# RP2350_CWHusky.net
KiCad netlist of a schematic drawn in Altium Designer
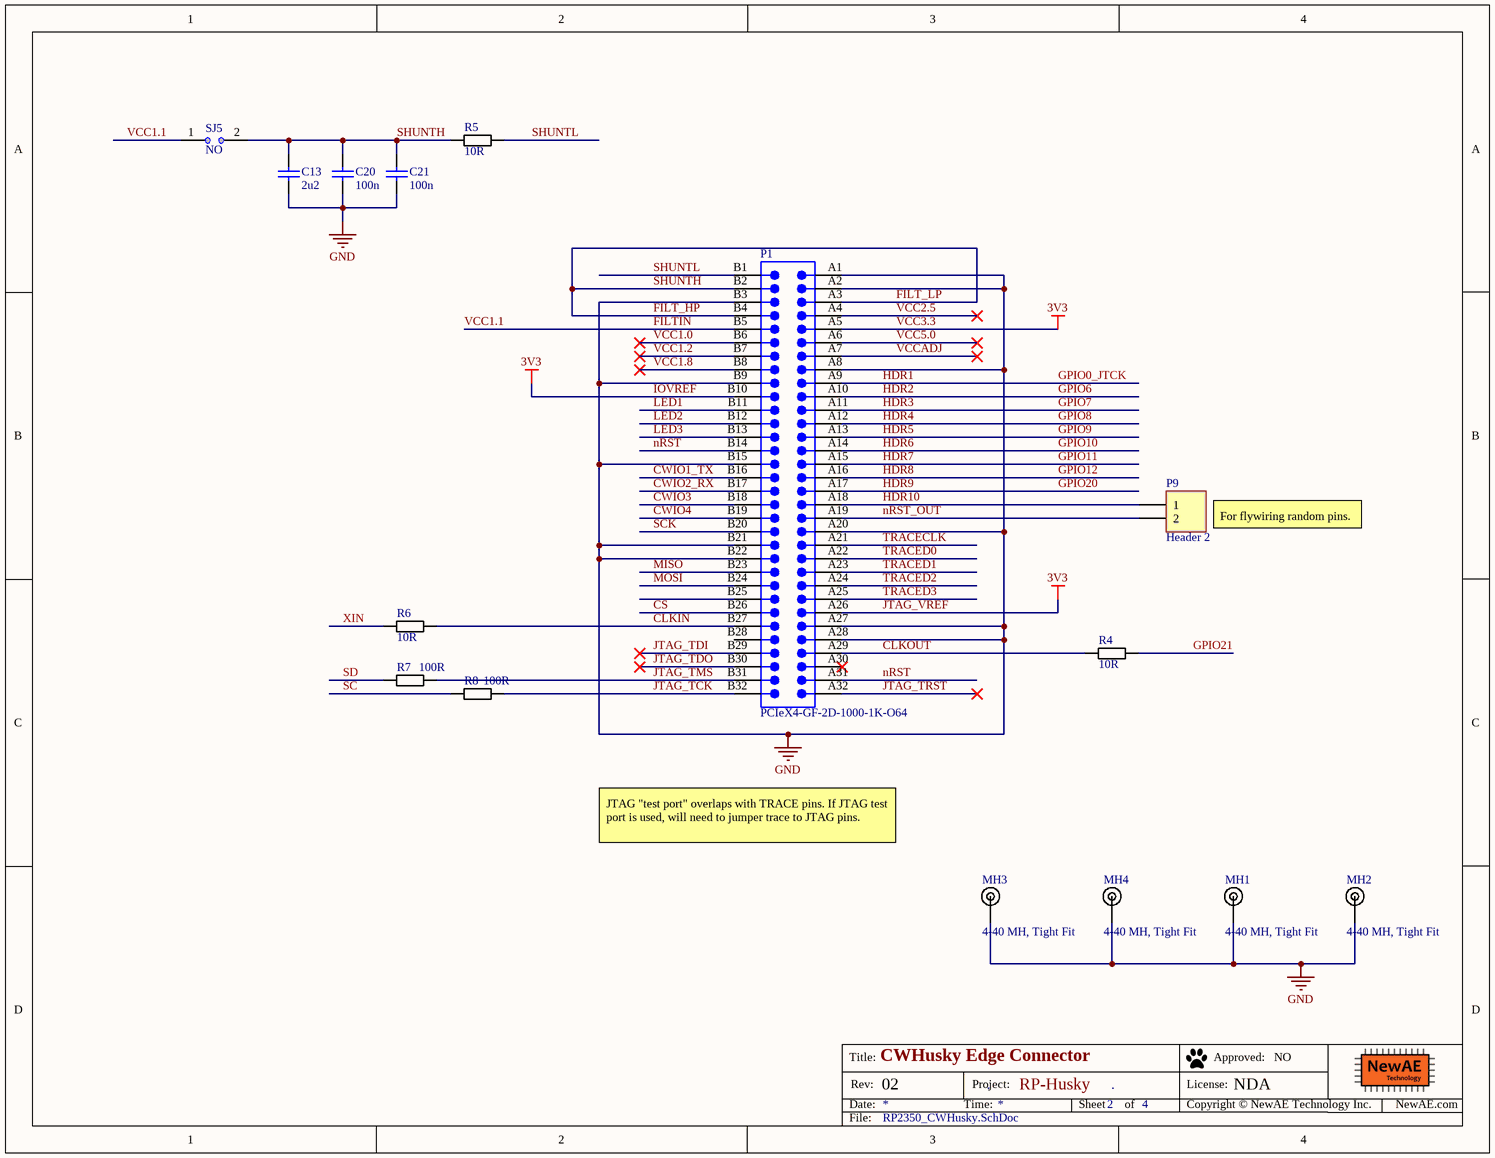
[diagram p0: RP2350_CWHusky.SchDoc]

(export (version "E")
  (design (tool "Eeschema 10.0.6"))
  (components
    (comp (ref "C13")
      (value "2u2")
      (footprint "CAPC0603_M")
      (description "2u2, 0603")
      (fields (field (name "PART NUMBER") "CCHIP-2u2-0603"))
      (libsource (lib "NewAE_AltiumLib") (part "CAP"))
    )
    (comp (ref "C20")
      (value "100n")
      (footprint "CAPC0603_M")
      (description "100n, 0603")
      (fields (field (name "PART NUMBER") "CCHIP-100n-0603"))
      (libsource (lib "NewAE_AltiumLib") (part "CAP"))
    )
    (comp (ref "C21")
      (value "100n")
      (footprint "CAPC0603_M")
      (description "100n, 0603")
      (fields (field (name "PART NUMBER") "CCHIP-100n-0603"))
      (libsource (lib "NewAE_AltiumLib") (part "CAP"))
    )
    (comp (ref "MH1")
      (value "4-40 MH, Tight Fit")
      (footprint "MOUNT_#4_TIGHT")
      (description "Machine screw 4-40 Mounting Hole")
      (fields (field (name "PART NUMBER") "MOUNT_#4_TIGHT"))
      (libsource (lib "NewAE_AltiumLib") (part "Mounting_Hole"))
    )
    (comp (ref "MH2")
      (value "4-40 MH, Tight Fit")
      (footprint "MOUNT_#4_TIGHT")
      (description "Machine screw 4-40 Mounting Hole")
      (fields (field (name "PART NUMBER") "MOUNT_#4_TIGHT"))
      (libsource (lib "NewAE_AltiumLib") (part "Mounting_Hole"))
    )
    (comp (ref "MH3")
      (value "4-40 MH, Tight Fit")
      (footprint "MOUNT_#4_TIGHT")
      (description "Machine screw 4-40 Mounting Hole")
      (fields (field (name "PART NUMBER") "MOUNT_#4_TIGHT"))
      (libsource (lib "NewAE_AltiumLib") (part "Mounting_Hole"))
    )
    (comp (ref "MH4")
      (value "4-40 MH, Tight Fit")
      (footprint "MOUNT_#4_TIGHT")
      (description "Machine screw 4-40 Mounting Hole")
      (fields (field (name "PART NUMBER") "MOUNT_#4_TIGHT"))
      (libsource (lib "NewAE_AltiumLib") (part "Mounting_Hole"))
    )
    (comp (ref "P1")
      (value "PCIeX4-GF-2D-1000-1K-O64")
      (footprint "PCIeX4-GF-2D-1000-1K-O64")
      (description "Golden finger, PCIeX4, Dual, Opposite, Pitch 1mm, 64-Position")
      (fields (field (name "PUBLISHER") "Altium"))
      (libsource (lib "Altium Content Vault") (part "PCIeX4-GF-2D-1000-1K-O64"))
    )
    (comp (ref "P9")
      (value "Header 2")
      (footprint "HDR1X2")
      (description "Header, 2-Pin")
      (fields (field (name "PUBLISHER") "Altium Limited"))
      (libsource (lib "Miscellaneous Connectors") (part "Header 2"))
    )
    (comp (ref "R4")
      (value "10R")
      (footprint "RESC1608X55N")
      (description "10R res, 0603, 1%, 1/10W")
      (fields (field (name "PART NUMBER") "RCHIP-10R-0603") (field (name "TOLERANCE") "1%"))
      (libsource (lib "NewAE_AltiumLib") (part "RES-EU"))
    )
    (comp (ref "R5")
      (value "10R")
      (footprint "RESC1608X55N")
      (description "10R res, 0603, 1%, 1/10W")
      (fields (field (name "PART NUMBER") "RCHIP-10R-0603") (field (name "TOLERANCE") "1%"))
      (libsource (lib "NewAE_AltiumLib") (part "RES-EU"))
    )
    (comp (ref "R6")
      (value "10R")
      (footprint "RESC1608X55N")
      (description "10R res, 0603, 1%, 1/10W")
      (fields (field (name "PART NUMBER") "RCHIP-10R-0603") (field (name "TOLERANCE") "1%"))
      (libsource (lib "NewAE_AltiumLib") (part "RES-EU"))
    )
    (comp (ref "R7")
      (value "100R")
      (footprint "RESC1608X55N")
      (description "100R res, 0603, 1%, 1/10W")
      (fields (field (name "PART NUMBER") "RCHIP-100R-0603") (field (name "TOLERANCE") "1%"))
      (libsource (lib "NewAE_AltiumLib") (part "RES-EU"))
    )
    (comp (ref "R8")
      (value "100R")
      (footprint "RESC1608X55N")
      (description "100R res, 0603, 1%, 1/10W")
      (fields (field (name "PART NUMBER") "RCHIP-100R-0603") (field (name "TOLERANCE") "1%"))
      (libsource (lib "NewAE_AltiumLib") (part "RES-EU"))
    )
    (comp (ref "SJ5")
      (value "NO")
      (footprint "SJ_2S_NO")
      (description "Solder Jumper, NO")
      (fields (field (name "PART NUMBER") "SJ_2S_NO"))
      (libsource (lib "NewAE_AltiumLib") (part "SJ_2S_NO"))
    )
  )
  (nets
    (net (code "1") (name "/CLKIN") (class "Default")
      (node (ref "P1") (pin "B27") (pinfunction "B27_B27") (pintype "passive"))
      (node (ref "R6") (pin "2") (pinfunction "2_2") (pintype "passive"))
    )
    (net (code "2") (name "/CLKOUT") (class "Default")
      (node (ref "P1") (pin "A29") (pinfunction "A29_A29") (pintype "passive"))
      (node (ref "R4") (pin "1") (pinfunction "1_1") (pintype "passive"))
    )
    (net (code "3") (name "/CS") (class "Default")
      (node (ref "P1") (pin "B26") (pinfunction "B26_B26") (pintype "passive"))
    )
    (net (code "4") (name "/CWIO1_TX") (class "Default")
      (node (ref "P1") (pin "B16") (pinfunction "B16_B16") (pintype "passive"))
    )
    (net (code "5") (name "/CWIO2_RX") (class "Default")
      (node (ref "P1") (pin "B17") (pinfunction "B17_B17") (pintype "passive"))
    )
    (net (code "6") (name "/CWIO3") (class "Default")
      (node (ref "P1") (pin "B18") (pinfunction "B18_B18") (pintype "passive"))
    )
    (net (code "7") (name "/CWIO4") (class "Default")
      (node (ref "P1") (pin "B19") (pinfunction "B19_B19") (pintype "passive"))
    )
    (net (code "8") (name "/FILTIN") (class "Default")
      (node (ref "P1") (pin "B5") (pinfunction "B5_B5") (pintype "passive"))
      (node (ref "SJ5") (pin "1") (pinfunction "1_1") (pintype "passive"))
    )
    (net (code "9") (name "/FILT_HP") (class "Default")
      (node (ref "C13") (pin "1") (pinfunction "1_1") (pintype "passive"))
      (node (ref "C20") (pin "1") (pinfunction "1_1") (pintype "passive"))
      (node (ref "C21") (pin "1") (pinfunction "1_1") (pintype "passive"))
      (node (ref "P1") (pin "A3") (pinfunction "A3_A3") (pintype "passive"))
      (node (ref "P1") (pin "B2") (pinfunction "B2_B2") (pintype "passive"))
      (node (ref "P1") (pin "B4") (pinfunction "B4_B4") (pintype "passive"))
      (node (ref "R5") (pin "1") (pinfunction "1_1") (pintype "passive"))
      (node (ref "SJ5") (pin "2") (pinfunction "2_2") (pintype "passive"))
    )
    (net (code "10") (name "/GPIO0_JTCK") (class "Default")
      (node (ref "P1") (pin "A9") (pinfunction "A9_A9") (pintype "passive"))
    )
    (net (code "11") (name "/GPIO6") (class "Default")
      (node (ref "P1") (pin "A10") (pinfunction "A10_A10") (pintype "passive"))
    )
    (net (code "12") (name "/GPIO7") (class "Default")
      (node (ref "P1") (pin "A11") (pinfunction "A11_A11") (pintype "passive"))
    )
    (net (code "13") (name "/GPIO8") (class "Default")
      (node (ref "P1") (pin "A12") (pinfunction "A12_A12") (pintype "passive"))
    )
    (net (code "14") (name "/GPIO9") (class "Default")
      (node (ref "P1") (pin "A13") (pinfunction "A13_A13") (pintype "passive"))
    )
    (net (code "15") (name "/GPIO10") (class "Default")
      (node (ref "P1") (pin "A14") (pinfunction "A14_A14") (pintype "passive"))
    )
    (net (code "16") (name "/GPIO11") (class "Default")
      (node (ref "P1") (pin "A15") (pinfunction "A15_A15") (pintype "passive"))
    )
    (net (code "17") (name "/GPIO12") (class "Default")
      (node (ref "P1") (pin "A16") (pinfunction "A16_A16") (pintype "passive"))
    )
    (net (code "18") (name "/GPIO20") (class "Default")
      (node (ref "P1") (pin "A17") (pinfunction "A17_A17") (pintype "passive"))
    )
    (net (code "19") (name "/GPIO21") (class "Default")
      (node (ref "R4") (pin "2") (pinfunction "2_2") (pintype "passive"))
    )
    (net (code "20") (name "/HDR10") (class "Default")
      (node (ref "P1") (pin "A18") (pinfunction "A18_A18") (pintype "passive"))
      (node (ref "P9") (pin "1") (pinfunction "1_1") (pintype "passive"))
    )
    (net (code "21") (name "/JTAG_TCK") (class "Default")
      (node (ref "P1") (pin "B32") (pinfunction "B32_B32") (pintype "passive"))
      (node (ref "R8") (pin "2") (pinfunction "2_2") (pintype "passive"))
    )
    (net (code "22") (name "/JTAG_TDI") (class "Default")
      (node (ref "P1") (pin "B29") (pinfunction "B29_B29") (pintype "passive+no_connect"))
    )
    (net (code "23") (name "/JTAG_TDO") (class "Default")
      (node (ref "P1") (pin "B30") (pinfunction "B30_B30") (pintype "passive+no_connect"))
    )
    (net (code "24") (name "/JTAG_TMS") (class "Default")
      (node (ref "P1") (pin "B31") (pinfunction "B31_B31") (pintype "passive"))
      (node (ref "R7") (pin "2") (pinfunction "2_2") (pintype "passive"))
    )
    (net (code "25") (name "/JTAG_TRST") (class "Default")
      (node (ref "P1") (pin "A32") (pinfunction "A32_A32") (pintype "passive+no_connect"))
    )
    (net (code "26") (name "/LED1") (class "Default")
      (node (ref "P1") (pin "B11") (pinfunction "B11_B11") (pintype "passive"))
    )
    (net (code "27") (name "/LED2") (class "Default")
      (node (ref "P1") (pin "B12") (pinfunction "B12_B12") (pintype "passive"))
    )
    (net (code "28") (name "/LED3") (class "Default")
      (node (ref "P1") (pin "B13") (pinfunction "B13_B13") (pintype "passive"))
    )
    (net (code "29") (name "/MISO") (class "Default")
      (node (ref "P1") (pin "B23") (pinfunction "B23_B23") (pintype "passive"))
    )
    (net (code "30") (name "/MOSI") (class "Default")
      (node (ref "P1") (pin "B24") (pinfunction "B24_B24") (pintype "passive"))
    )
    (net (code "31") (name "/SC") (class "Default")
      (node (ref "R8") (pin "1") (pinfunction "1_1") (pintype "passive"))
    )
    (net (code "32") (name "/SCK") (class "Default")
      (node (ref "P1") (pin "B20") (pinfunction "B20_B20") (pintype "passive"))
    )
    (net (code "33") (name "/SD") (class "Default")
      (node (ref "R7") (pin "1") (pinfunction "1_1") (pintype "passive"))
    )
    (net (code "34") (name "/SHUNTL") (class "Default")
      (node (ref "P1") (pin "B1") (pinfunction "B1_B1") (pintype "passive"))
      (node (ref "R5") (pin "2") (pinfunction "2_2") (pintype "passive"))
    )
    (net (code "35") (name "/TRACECLK") (class "Default")
      (node (ref "P1") (pin "A21") (pinfunction "A21_A21") (pintype "passive"))
    )
    (net (code "36") (name "/TRACED0") (class "Default")
      (node (ref "P1") (pin "A22") (pinfunction "A22_A22") (pintype "passive"))
    )
    (net (code "37") (name "/TRACED1") (class "Default")
      (node (ref "P1") (pin "A23") (pinfunction "A23_A23") (pintype "passive"))
    )
    (net (code "38") (name "/TRACED2") (class "Default")
      (node (ref "P1") (pin "A24") (pinfunction "A24_A24") (pintype "passive"))
    )
    (net (code "39") (name "/TRACED3") (class "Default")
      (node (ref "P1") (pin "A25") (pinfunction "A25_A25") (pintype "passive"))
    )
    (net (code "40") (name "/VCC1.0") (class "Default")
      (node (ref "P1") (pin "B6") (pinfunction "B6_B6") (pintype "passive+no_connect"))
    )
    (net (code "41") (name "/VCC1.2") (class "Default")
      (node (ref "P1") (pin "B7") (pinfunction "B7_B7") (pintype "passive+no_connect"))
    )
    (net (code "42") (name "/VCC1.8") (class "Default")
      (node (ref "P1") (pin "B8") (pinfunction "B8_B8") (pintype "passive+no_connect"))
    )
    (net (code "43") (name "/VCC2.5") (class "Default")
      (node (ref "P1") (pin "A4") (pinfunction "A4_A4") (pintype "passive+no_connect"))
    )
    (net (code "44") (name "/VCC5.0") (class "Default")
      (node (ref "P1") (pin "A6") (pinfunction "A6_A6") (pintype "passive+no_connect"))
    )
    (net (code "45") (name "/VCCADJ") (class "Default")
      (node (ref "P1") (pin "A7") (pinfunction "A7_A7") (pintype "passive+no_connect"))
    )
    (net (code "46") (name "/XIN") (class "Default")
      (node (ref "R6") (pin "1") (pinfunction "1_1") (pintype "passive"))
    )
    (net (code "47") (name "/nRST") (class "Default")
      (node (ref "P1") (pin "A31") (pinfunction "A31_A31") (pintype "passive"))
      (node (ref "P1") (pin "B14") (pinfunction "B14_B14") (pintype "passive"))
    )
    (net (code "48") (name "/nRST_OUT") (class "Default")
      (node (ref "P1") (pin "A19") (pinfunction "A19_A19") (pintype "passive"))
      (node (ref "P9") (pin "2") (pinfunction "2_2") (pintype "passive"))
    )
    (net (code "49") (name "3V3") (class "Default")
      (node (ref "P1") (pin "A26") (pinfunction "A26_A26") (pintype "passive"))
      (node (ref "P1") (pin "A5") (pinfunction "A5_A5") (pintype "passive"))
      (node (ref "P1") (pin "B10") (pinfunction "B10_B10") (pintype "passive"))
    )
    (net (code "50") (name "GND") (class "Default")
      (node (ref "C13") (pin "2") (pinfunction "2_2") (pintype "passive"))
      (node (ref "C20") (pin "2") (pinfunction "2_2") (pintype "passive"))
      (node (ref "C21") (pin "2") (pinfunction "2_2") (pintype "passive"))
      (node (ref "MH1") (pin "1") (pinfunction "1_1") (pintype "passive"))
      (node (ref "MH2") (pin "1") (pinfunction "1_1") (pintype "passive"))
      (node (ref "MH3") (pin "1") (pinfunction "1_1") (pintype "passive"))
      (node (ref "MH4") (pin "1") (pinfunction "1_1") (pintype "passive"))
      (node (ref "P1") (pin "A1") (pinfunction "A1_A1") (pintype "passive"))
      (node (ref "P1") (pin "A2") (pinfunction "A2_A2") (pintype "passive"))
      (node (ref "P1") (pin "A20") (pinfunction "A20_A20") (pintype "passive"))
      (node (ref "P1") (pin "A27") (pinfunction "A27_A27") (pintype "passive"))
      (node (ref "P1") (pin "A28") (pinfunction "A28_A28") (pintype "passive"))
      (node (ref "P1") (pin "A8") (pinfunction "A8_A8") (pintype "passive"))
      (node (ref "P1") (pin "B15") (pinfunction "B15_B15") (pintype "passive"))
      (node (ref "P1") (pin "B21") (pinfunction "B21_B21") (pintype "passive"))
      (node (ref "P1") (pin "B22") (pinfunction "B22_B22") (pintype "passive"))
      (node (ref "P1") (pin "B3") (pinfunction "B3_B3") (pintype "passive"))
      (node (ref "P1") (pin "B9") (pinfunction "B9_B9") (pintype "passive"))
    )
    (net (code "51") (name "unconnected-(P1-PadA30)") (class "Default")
      (node (ref "P1") (pin "A30") (pinfunction "A30_A30") (pintype "passive+no_connect"))
    )
    (net (code "52") (name "unconnected-(P1-PadB25)") (class "Default")
      (node (ref "P1") (pin "B25") (pinfunction "B25_B25") (pintype "passive"))
    )
    (net (code "53") (name "unconnected-(P1-PadB28)") (class "Default")
      (node (ref "P1") (pin "B28") (pinfunction "B28_B28") (pintype "passive"))
    )
  )
)
